# TR_i3_6A_Module_v10.net
KiCad netlist of a schematic drawn in EAGLE
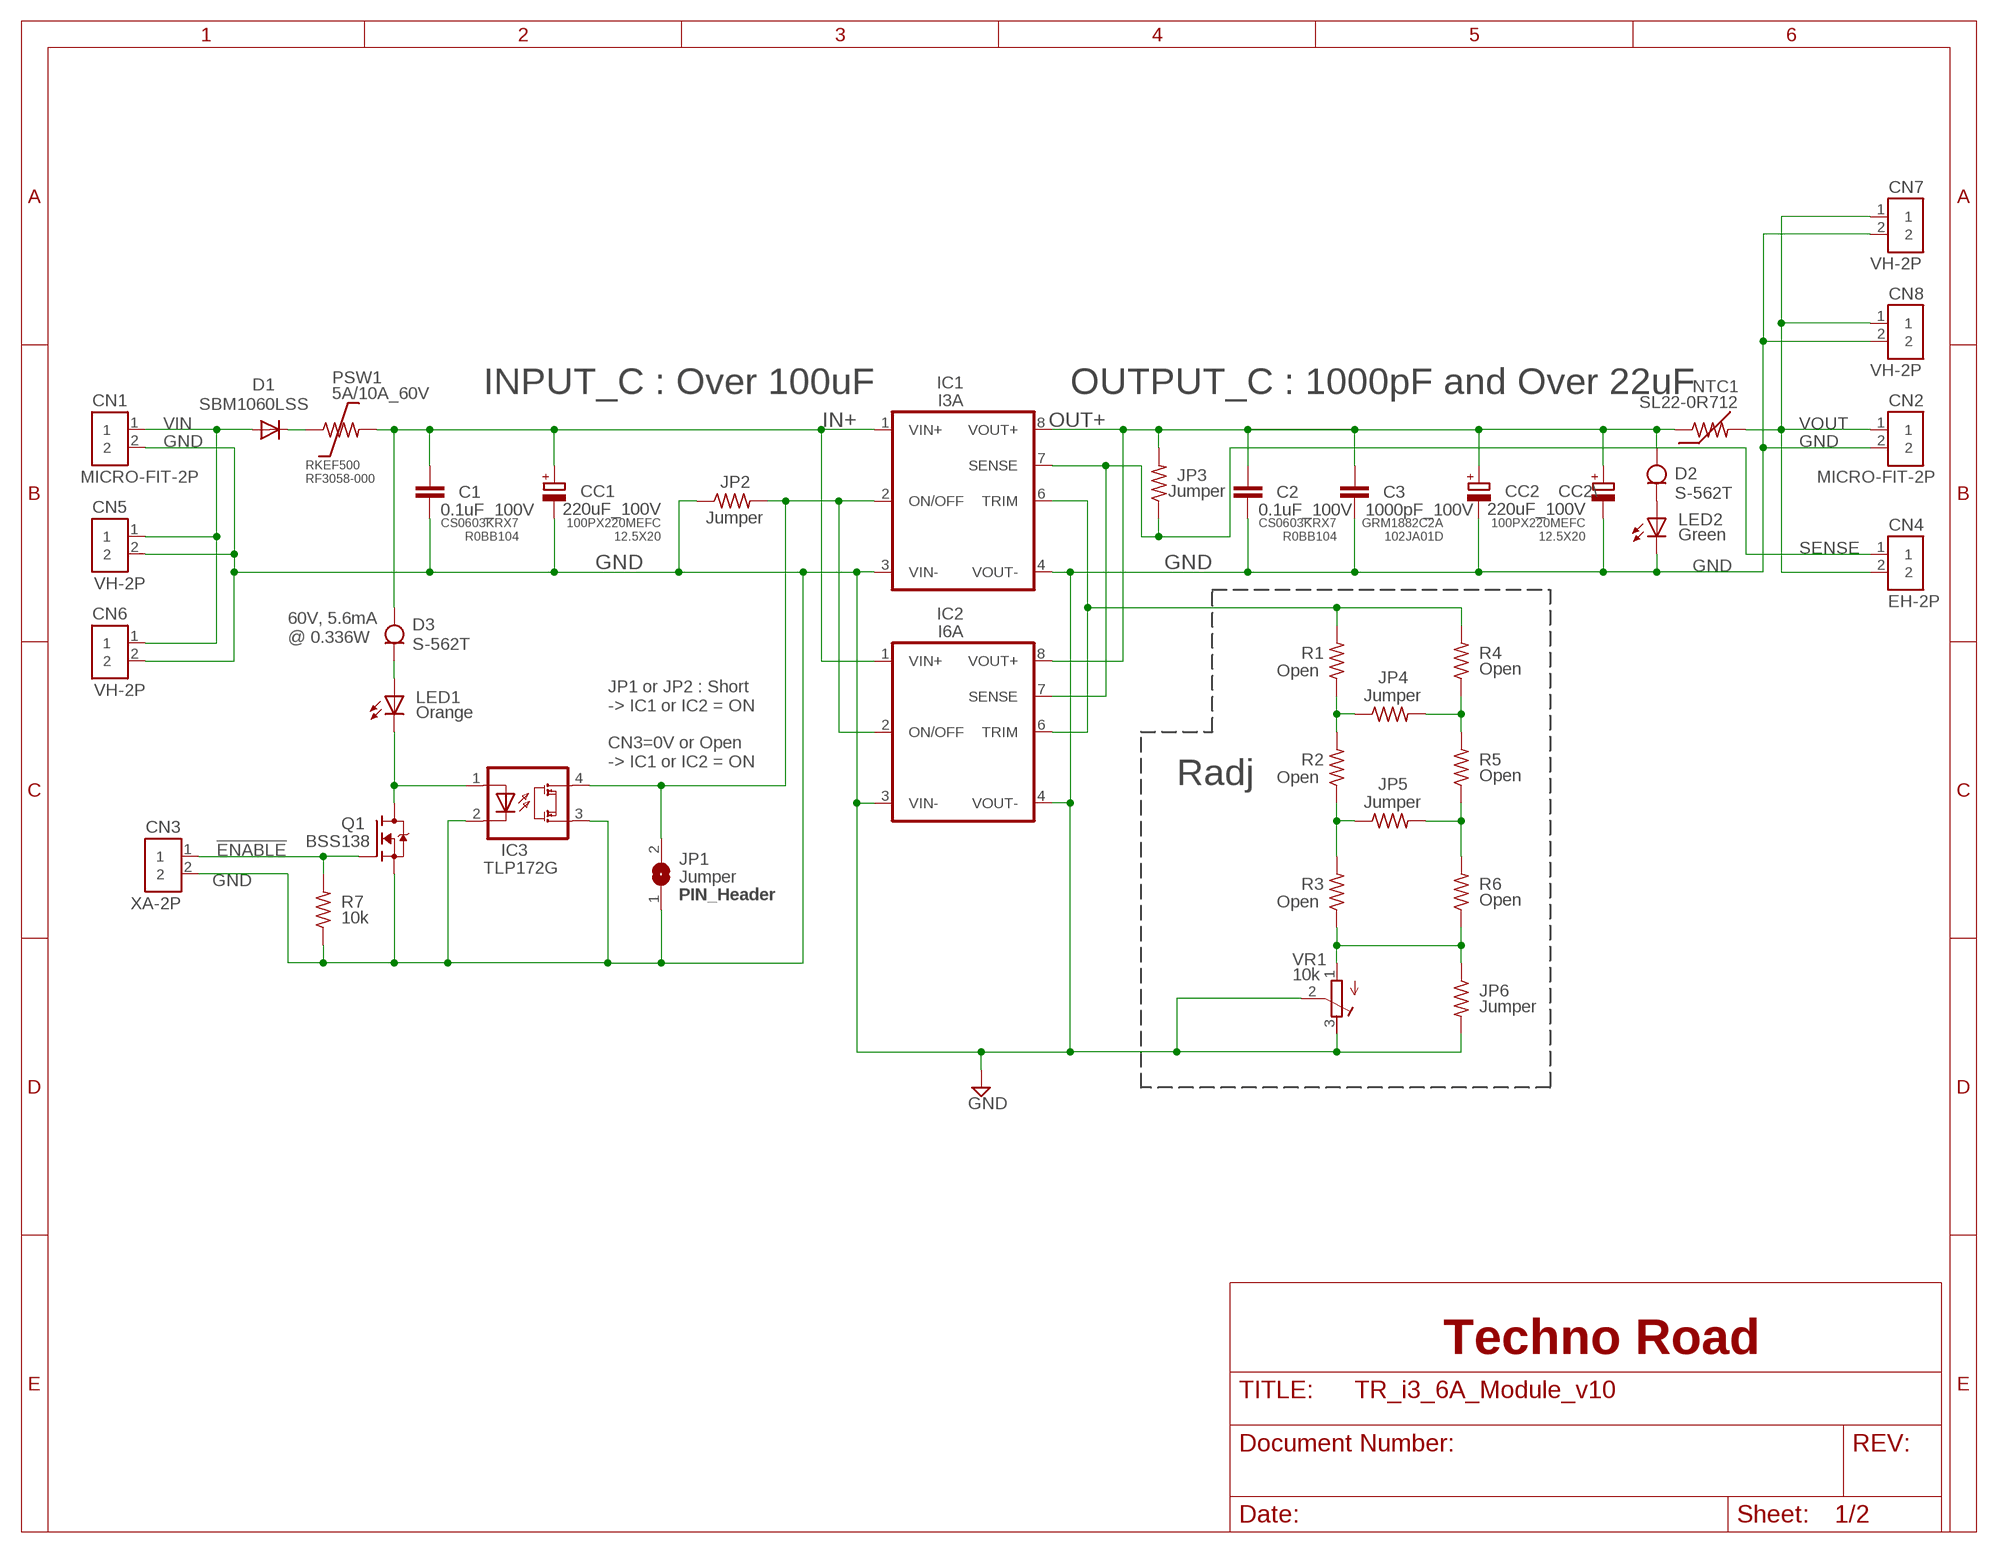
[diagram p0: schematic, sheet 1]

(export (version "E")
  (design (tool "Eeschema 10.0.6"))
  (components
    (comp (ref "C1")
      (value "0.1uF_100V")
      (footprint "eagle-import:C1608")
      (libsource (lib "eagle-import") (part "C1608"))
    )
    (comp (ref "C2")
      (value "0.1uF_100V")
      (footprint "eagle-import:C1608")
      (libsource (lib "eagle-import") (part "C1608"))
    )
    (comp (ref "C3")
      (value "1000pF_100V")
      (footprint "eagle-import:C1608")
      (libsource (lib "eagle-import") (part "C1608"))
    )
    (comp (ref "CC1")
      (value "220uF_100V")
      (footprint "eagle-import:CC0510")
      (libsource (lib "eagle-import") (part "CC0510"))
    )
    (comp (ref "CC2")
      (value "220uF_100V")
      (footprint "eagle-import:CC0510")
      (libsource (lib "eagle-import") (part "CC0510"))
    )
    (comp (ref "CC2\\")
      (value "CPOL-EUE7.5-16")
      (footprint "eagle-import:E7,5-16")
      (libsource (lib "eagle-import") (part "CPOL-EUE7.5-16"))
    )
    (comp (ref "CN1")
      (value "MICRO-FIT-2P")
      (footprint "eagle-import:MICRO-FIT-2T")
      (libsource (lib "eagle-import") (part "2PMICRO-FIT"))
    )
    (comp (ref "CN2")
      (value "MICRO-FIT-2P")
      (footprint "eagle-import:MICRO-FIT-2T")
      (libsource (lib "eagle-import") (part "2PMICRO-FIT"))
    )
    (comp (ref "CN3")
      (value "XA-2P")
      (footprint "eagle-import:XA-2P_NH")
      (libsource (lib "eagle-import") (part "2PXA_NH"))
    )
    (comp (ref "CN4")
      (value "EH-2P")
      (footprint "eagle-import:EH-2P")
      (libsource (lib "eagle-import") (part "2PEH"))
    )
    (comp (ref "CN5")
      (value "VH-2P")
      (footprint "eagle-import:VH-2P")
      (libsource (lib "eagle-import") (part "2PVH"))
    )
    (comp (ref "CN6")
      (value "VH-2P")
      (footprint "eagle-import:VH-2P")
      (libsource (lib "eagle-import") (part "2PVH"))
    )
    (comp (ref "CN7")
      (value "VH-2P")
      (footprint "eagle-import:VH-2P")
      (libsource (lib "eagle-import") (part "2PVH"))
    )
    (comp (ref "CN8")
      (value "VH-2P")
      (footprint "eagle-import:VH-2P")
      (libsource (lib "eagle-import") (part "2PVH"))
    )
    (comp (ref "D1")
      (value "SBM1060LSS")
      (footprint "eagle-import:12.7MM")
      (libsource (lib "eagle-import") (part "D12.7"))
    )
    (comp (ref "D2")
      (value "S-562T")
      (footprint "eagle-import:S-XXXT")
      (libsource (lib "eagle-import") (part "CRDS-XXXT"))
    )
    (comp (ref "D3")
      (value "S-562T")
      (footprint "eagle-import:S-XXXT")
      (libsource (lib "eagle-import") (part "CRDS-XXXT"))
    )
    (comp (ref "IC1")
      (value "I3A")
      (footprint "eagle-import:I3A_SERIES")
      (libsource (lib "eagle-import") (part "I3A/I6A_SEREISI3A"))
    )
    (comp (ref "IC2")
      (value "I6A")
      (footprint "eagle-import:I6A_SERIES")
      (libsource (lib "eagle-import") (part "I3A/I6A_SEREISI6A"))
    )
    (comp (ref "IC3")
      (value "TLP172G")
      (footprint "eagle-import:11-5H1")
      (libsource (lib "eagle-import") (part "TLP172"))
    )
    (comp (ref "JP1")
      (value "Jumper")
      (footprint "eagle-import:JP1D_HOLE")
      (libsource (lib "eagle-import") (part "JP1D"))
    )
    (comp (ref "JP2")
      (value "Jumper")
      (footprint "eagle-import:R1608_LARGE_PAD")
      (libsource (lib "eagle-import") (part "R1608_LARGE_PAD"))
    )
    (comp (ref "JP3")
      (value "Jumper")
      (footprint "eagle-import:R1608_LARGE_PAD")
      (libsource (lib "eagle-import") (part "R1608_LARGE_PAD"))
    )
    (comp (ref "JP4")
      (value "Jumper")
      (footprint "eagle-import:R1608_LARGE_PAD")
      (libsource (lib "eagle-import") (part "R1608_LARGE_PAD"))
    )
    (comp (ref "JP5")
      (value "Jumper")
      (footprint "eagle-import:R1608_LARGE_PAD")
      (libsource (lib "eagle-import") (part "R1608_LARGE_PAD"))
    )
    (comp (ref "JP6")
      (value "Jumper")
      (footprint "eagle-import:R1608_LARGE_PAD")
      (libsource (lib "eagle-import") (part "R1608_LARGE_PAD"))
    )
    (comp (ref "LED1")
      (value "Orange")
      (footprint "eagle-import:SML1608")
      (libsource (lib "eagle-import") (part "LEDSML0603"))
    )
    (comp (ref "LED2")
      (value "Green")
      (footprint "eagle-import:SML1608")
      (libsource (lib "eagle-import") (part "LEDSML0603"))
    )
    (comp (ref "NTC1")
      (value "SL22-0R712")
      (footprint "eagle-import:SL22")
      (libsource (lib "eagle-import") (part "NTCSL22"))
    )
    (comp (ref "PSW1")
      (value "5A/10A_60V")
      (footprint "eagle-import:PSW-10.16MM_4MM")
      (libsource (lib "eagle-import") (part "PSW10.16MM_4MM"))
    )
    (comp (ref "Q1")
      (value "BSS138")
      (footprint "eagle-import:SOT-23-3")
      (libsource (lib "eagle-import") (part "BSS138"))
    )
    (comp (ref "R1")
      (value "Open")
      (footprint "eagle-import:R1608_LARGE_PAD")
      (libsource (lib "eagle-import") (part "R1608_LARGE_PAD"))
    )
    (comp (ref "R2")
      (value "Open")
      (footprint "eagle-import:R1608_LARGE_PAD")
      (libsource (lib "eagle-import") (part "R1608_LARGE_PAD"))
    )
    (comp (ref "R3")
      (value "Open")
      (footprint "eagle-import:R1608_LARGE_PAD")
      (libsource (lib "eagle-import") (part "R1608_LARGE_PAD"))
    )
    (comp (ref "R4")
      (value "Open")
      (footprint "eagle-import:R1608_LARGE_PAD")
      (libsource (lib "eagle-import") (part "R1608_LARGE_PAD"))
    )
    (comp (ref "R5")
      (value "Open")
      (footprint "eagle-import:R1608_LARGE_PAD")
      (libsource (lib "eagle-import") (part "R1608_LARGE_PAD"))
    )
    (comp (ref "R6")
      (value "Open")
      (footprint "eagle-import:R1608_LARGE_PAD")
      (libsource (lib "eagle-import") (part "R1608_LARGE_PAD"))
    )
    (comp (ref "R7")
      (value "10k")
      (footprint "eagle-import:R1608_LARGE_PAD")
      (libsource (lib "eagle-import") (part "R1608_LARGE_PAD"))
    )
    (comp (ref "VR1")
      (value "10k")
      (footprint "eagle-import:3361P")
      (libsource (lib "eagle-import") (part "R-TRIM3361P"))
    )
  )
  (nets
    (net (code "1") (name "GND") (class "Default")
      (node (ref "C1") (pin "2") (pinfunction "2_2") (pintype "passive"))
      (node (ref "C2") (pin "2") (pinfunction "2_2") (pintype "passive"))
      (node (ref "C3") (pin "2") (pinfunction "2_2") (pintype "passive"))
      (node (ref "CC1") (pin "-") (pinfunction "-_-") (pintype "passive"))
      (node (ref "CC2") (pin "-") (pinfunction "-_-") (pintype "passive"))
      (node (ref "CC2\\") (pin "-") (pinfunction "-_-") (pintype "passive"))
      (node (ref "CN1") (pin "2") (pinfunction "2_2") (pintype "passive"))
      (node (ref "CN2") (pin "2") (pinfunction "2_2") (pintype "passive"))
      (node (ref "CN3") (pin "2") (pinfunction "2_2") (pintype "passive"))
      (node (ref "CN5") (pin "2") (pinfunction "2_2") (pintype "passive"))
      (node (ref "CN6") (pin "2") (pinfunction "2_2") (pintype "passive"))
      (node (ref "CN7") (pin "2") (pinfunction "2_2") (pintype "passive"))
      (node (ref "CN8") (pin "2") (pinfunction "2_2") (pintype "passive"))
      (node (ref "IC1") (pin "3") (pinfunction "VIN-_3") (pintype "passive"))
      (node (ref "IC1") (pin "4") (pinfunction "VOUT-_4") (pintype "passive"))
      (node (ref "IC2") (pin "3") (pinfunction "VIN-_3") (pintype "passive"))
      (node (ref "IC2") (pin "4") (pinfunction "VOUT-_4") (pintype "passive"))
      (node (ref "IC3") (pin "2") (pinfunction "C1_2") (pintype "passive"))
      (node (ref "IC3") (pin "3") (pinfunction "DRN1_3") (pintype "passive"))
      (node (ref "JP1") (pin "1") (pinfunction "1_1") (pintype "passive"))
      (node (ref "JP2") (pin "1") (pinfunction "1_1") (pintype "passive"))
      (node (ref "JP6") (pin "2") (pinfunction "2_2") (pintype "passive"))
      (node (ref "LED2") (pin "C") (pinfunction "C_C") (pintype "passive"))
      (node (ref "Q1") (pin "2") (pinfunction "S_2") (pintype "passive"))
      (node (ref "R7") (pin "1") (pinfunction "1_1") (pintype "passive"))
      (node (ref "VR1") (pin "2") (pinfunction "S_2") (pintype "passive"))
      (node (ref "VR1") (pin "3") (pinfunction "E_3") (pintype "passive"))
    )
    (net (code "2") (name "IN+") (class "Default")
      (node (ref "C1") (pin "1") (pinfunction "1_1") (pintype "passive"))
      (node (ref "CC1") (pin "+") (pinfunction "+_+") (pintype "passive"))
      (node (ref "D3") (pin "A") (pinfunction "A_A") (pintype "passive"))
      (node (ref "IC1") (pin "1") (pinfunction "VIN+_1") (pintype "passive"))
      (node (ref "IC2") (pin "1") (pinfunction "VIN+_1") (pintype "passive"))
      (node (ref "PSW1") (pin "2") (pinfunction "2_2") (pintype "passive"))
    )
    (net (code "3") (name "Net-(D1-C)") (class "Default")
      (node (ref "D1") (pin "2") (pinfunction "C_2") (pintype "passive"))
      (node (ref "PSW1") (pin "1") (pinfunction "1_1") (pintype "passive"))
    )
    (net (code "4") (name "Net-(D2-PadC)") (class "Default")
      (node (ref "D2") (pin "C") (pinfunction "C_C") (pintype "passive"))
      (node (ref "LED2") (pin "A") (pinfunction "A_A") (pintype "passive"))
    )
    (net (code "5") (name "Net-(D3-PadC)") (class "Default")
      (node (ref "D3") (pin "C") (pinfunction "C_C") (pintype "passive"))
      (node (ref "LED1") (pin "A") (pinfunction "A_A") (pintype "passive"))
    )
    (net (code "6") (name "Net-(IC1-ON{slash}OFF)") (class "Default")
      (node (ref "IC1") (pin "2") (pinfunction "ON/OFF_2") (pintype "input"))
      (node (ref "IC2") (pin "2") (pinfunction "ON/OFF_2") (pintype "input"))
      (node (ref "IC3") (pin "4") (pinfunction "DRN2_4") (pintype "passive"))
      (node (ref "JP1") (pin "2") (pinfunction "2_2") (pintype "passive"))
      (node (ref "JP2") (pin "2") (pinfunction "2_2") (pintype "passive"))
    )
    (net (code "7") (name "Net-(IC1-TRIM)") (class "Default")
      (node (ref "IC1") (pin "6") (pinfunction "TRIM_6") (pintype "input"))
      (node (ref "IC2") (pin "6") (pinfunction "TRIM_6") (pintype "input"))
      (node (ref "R1") (pin "2") (pinfunction "2_2") (pintype "passive"))
      (node (ref "R4") (pin "2") (pinfunction "2_2") (pintype "passive"))
    )
    (net (code "8") (name "Net-(IC3-A1)") (class "Default")
      (node (ref "IC3") (pin "1") (pinfunction "A1_1") (pintype "passive"))
      (node (ref "LED1") (pin "C") (pinfunction "C_C") (pintype "passive"))
      (node (ref "Q1") (pin "3") (pinfunction "D_3") (pintype "passive"))
    )
    (net (code "9") (name "Net-(JP4-Pad1)") (class "Default")
      (node (ref "JP4") (pin "1") (pinfunction "1_1") (pintype "passive"))
      (node (ref "R1") (pin "1") (pinfunction "1_1") (pintype "passive"))
      (node (ref "R2") (pin "2") (pinfunction "2_2") (pintype "passive"))
    )
    (net (code "10") (name "Net-(JP4-Pad2)") (class "Default")
      (node (ref "JP4") (pin "2") (pinfunction "2_2") (pintype "passive"))
      (node (ref "R4") (pin "1") (pinfunction "1_1") (pintype "passive"))
      (node (ref "R5") (pin "2") (pinfunction "2_2") (pintype "passive"))
    )
    (net (code "11") (name "Net-(JP5-Pad1)") (class "Default")
      (node (ref "JP5") (pin "1") (pinfunction "1_1") (pintype "passive"))
      (node (ref "R2") (pin "1") (pinfunction "1_1") (pintype "passive"))
      (node (ref "R3") (pin "2") (pinfunction "2_2") (pintype "passive"))
    )
    (net (code "12") (name "Net-(JP5-Pad2)") (class "Default")
      (node (ref "JP5") (pin "2") (pinfunction "2_2") (pintype "passive"))
      (node (ref "R5") (pin "1") (pinfunction "1_1") (pintype "passive"))
      (node (ref "R6") (pin "2") (pinfunction "2_2") (pintype "passive"))
    )
    (net (code "13") (name "Net-(VR1-A)") (class "Default")
      (node (ref "JP6") (pin "1") (pinfunction "1_1") (pintype "passive"))
      (node (ref "R3") (pin "1") (pinfunction "1_1") (pintype "passive"))
      (node (ref "R6") (pin "1") (pinfunction "1_1") (pintype "passive"))
      (node (ref "VR1") (pin "1") (pinfunction "A_1") (pintype "passive"))
    )
    (net (code "14") (name "OUT+") (class "Default")
      (node (ref "C2") (pin "1") (pinfunction "1_1") (pintype "passive"))
      (node (ref "C3") (pin "1") (pinfunction "1_1") (pintype "passive"))
      (node (ref "CC2") (pin "+") (pinfunction "+_+") (pintype "passive"))
      (node (ref "CC2\\") (pin "+") (pinfunction "+_+") (pintype "passive"))
      (node (ref "D2") (pin "A") (pinfunction "A_A") (pintype "passive"))
      (node (ref "IC1") (pin "8") (pinfunction "VOUT+_8") (pintype "passive"))
      (node (ref "IC2") (pin "8") (pinfunction "VOUT+_8") (pintype "passive"))
      (node (ref "JP3") (pin "2") (pinfunction "2_2") (pintype "passive"))
      (node (ref "NTC1") (pin "1") (pinfunction "1_1") (pintype "passive"))
    )
    (net (code "15") (name "SENSE") (class "Default")
      (node (ref "CN4") (pin "1") (pinfunction "1_1") (pintype "passive"))
      (node (ref "IC1") (pin "7") (pinfunction "SENSE_7") (pintype "passive"))
      (node (ref "IC2") (pin "7") (pinfunction "SENSE_7") (pintype "passive"))
      (node (ref "JP3") (pin "1") (pinfunction "1_1") (pintype "passive"))
    )
    (net (code "16") (name "VIN") (class "Default")
      (node (ref "CN1") (pin "1") (pinfunction "1_1") (pintype "passive"))
      (node (ref "CN5") (pin "1") (pinfunction "1_1") (pintype "passive"))
      (node (ref "CN6") (pin "1") (pinfunction "1_1") (pintype "passive"))
      (node (ref "D1") (pin "1") (pinfunction "A_1") (pintype "passive"))
    )
    (net (code "17") (name "VOUT") (class "Default")
      (node (ref "CN2") (pin "1") (pinfunction "1_1") (pintype "passive"))
      (node (ref "CN4") (pin "2") (pinfunction "2_2") (pintype "passive"))
      (node (ref "CN7") (pin "1") (pinfunction "1_1") (pintype "passive"))
      (node (ref "CN8") (pin "1") (pinfunction "1_1") (pintype "passive"))
      (node (ref "NTC1") (pin "2") (pinfunction "2_2") (pintype "passive"))
    )
    (net (code "18") (name "~{ENABLE}") (class "Default")
      (node (ref "CN3") (pin "1") (pinfunction "1_1") (pintype "passive"))
      (node (ref "Q1") (pin "1") (pinfunction "G_1") (pintype "passive"))
      (node (ref "R7") (pin "2") (pinfunction "2_2") (pintype "passive"))
    )
  )
)
